# FPGA_CONFIG.net
KiCad netlist of a schematic drawn in Altium Designer
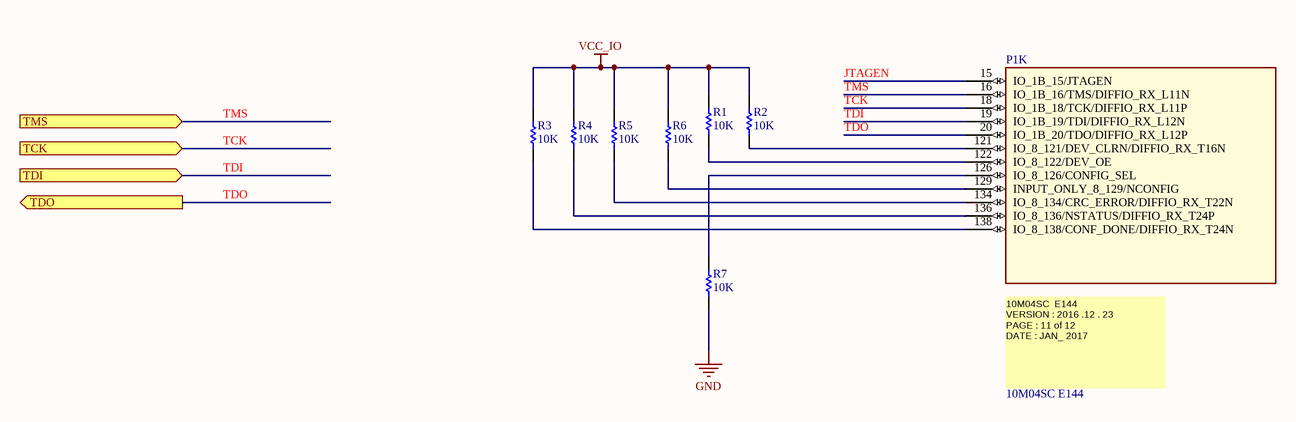
[diagram p0: FPGA_CONFIG.SchDoc]

(export (version "E")
  (design (tool "Eeschema 10.0.6"))
  (components
    (comp (ref "P1") (value "10M04SC E144") (libsource (lib "10m04sc_Library") (part "10M04SC E144")))
    (comp (ref "R1")
      (value "10K")
      (footprint "AXIAL-0.3")
      (description "Resistor")
      (fields (field (name "PUBLISHER") "Altium Limited"))
      (libsource (lib "Miscellaneous Devices") (part "Res1"))
    )
    (comp (ref "R2")
      (value "10K")
      (footprint "AXIAL-0.3")
      (description "Resistor")
      (fields (field (name "PUBLISHER") "Altium Limited"))
      (libsource (lib "Miscellaneous Devices") (part "Res1"))
    )
    (comp (ref "R3")
      (value "10K")
      (footprint "AXIAL-0.3")
      (description "Resistor")
      (fields (field (name "PUBLISHER") "Altium Limited"))
      (libsource (lib "Miscellaneous Devices") (part "Res1"))
    )
    (comp (ref "R4")
      (value "10K")
      (footprint "AXIAL-0.3")
      (description "Resistor")
      (fields (field (name "PUBLISHER") "Altium Limited"))
      (libsource (lib "Miscellaneous Devices") (part "Res1"))
    )
    (comp (ref "R5")
      (value "10K")
      (footprint "AXIAL-0.3")
      (description "Resistor")
      (fields (field (name "PUBLISHER") "Altium Limited"))
      (libsource (lib "Miscellaneous Devices") (part "Res1"))
    )
    (comp (ref "R6")
      (value "10K")
      (footprint "AXIAL-0.3")
      (description "Resistor")
      (fields (field (name "PUBLISHER") "Altium Limited"))
      (libsource (lib "Miscellaneous Devices") (part "Res1"))
    )
    (comp (ref "R7")
      (value "10K")
      (footprint "AXIAL-0.3")
      (description "Resistor")
      (fields (field (name "PUBLISHER") "Altium Limited"))
      (libsource (lib "Miscellaneous Devices") (part "Res1"))
    )
  )
  (nets
    (net (code "1") (name "/JTAGEN") (class "Default")
      (node (ref "P1") (pin "15") (pinfunction "IO_1B_15/JTAGEN_15") (pintype "bidirectional"))
    )
    (net (code "2") (name "/TCK") (class "Default")
      (node (ref "P1") (pin "18") (pinfunction "IO_1B_18/TCK/DIFFIO_RX_L11P_18") (pintype "bidirectional"))
    )
    (net (code "3") (name "/TDI") (class "Default")
      (node (ref "P1") (pin "19") (pinfunction "IO_1B_19/TDI/DIFFIO_RX_L12N_19") (pintype "bidirectional"))
    )
    (net (code "4") (name "/TDO") (class "Default")
      (node (ref "P1") (pin "20") (pinfunction "IO_1B_20/TDO/DIFFIO_RX_L12P_20") (pintype "bidirectional"))
    )
    (net (code "5") (name "/TMS") (class "Default")
      (node (ref "P1") (pin "16") (pinfunction "IO_1B_16/TMS/DIFFIO_RX_L11N_16") (pintype "bidirectional"))
    )
    (net (code "6") (name "GND") (class "Default")
      (node (ref "R7") (pin "1") (pinfunction "1_1") (pintype "passive"))
    )
    (net (code "7") (name "Net-(P1K-INPUT_ONLY_8_129{slash}NCONFIG)") (class "Default")
      (node (ref "P1") (pin "129") (pinfunction "INPUT_ONLY_8_129/NCONFIG_129") (pintype "bidirectional"))
      (node (ref "R6") (pin "1") (pinfunction "1_1") (pintype "passive"))
    )
    (net (code "8") (name "Net-(P1K-IO_8_121{slash}DEV_CLRN{slash}DIFFIO_RX_T16N)") (class "Default")
      (node (ref "P1") (pin "121") (pinfunction "IO_8_121/DEV_CLRN/DIFFIO_RX_T16N_121") (pintype "bidirectional"))
      (node (ref "R2") (pin "1") (pinfunction "1_1") (pintype "passive"))
    )
    (net (code "9") (name "Net-(P1K-IO_8_122{slash}DEV_OE)") (class "Default")
      (node (ref "P1") (pin "122") (pinfunction "IO_8_122/DEV_OE_122") (pintype "bidirectional"))
      (node (ref "R1") (pin "1") (pinfunction "1_1") (pintype "passive"))
    )
    (net (code "10") (name "Net-(P1K-IO_8_126{slash}CONFIG_SEL)") (class "Default")
      (node (ref "P1") (pin "126") (pinfunction "IO_8_126/CONFIG_SEL_126") (pintype "bidirectional"))
      (node (ref "R7") (pin "2") (pinfunction "2_2") (pintype "passive"))
    )
    (net (code "11") (name "Net-(P1K-IO_8_134{slash}CRC_ERROR{slash}DIFFIO_RX_T22N)") (class "Default")
      (node (ref "P1") (pin "134") (pinfunction "IO_8_134/CRC_ERROR/DIFFIO_RX_T22N_134") (pintype "bidirectional"))
      (node (ref "R5") (pin "1") (pinfunction "1_1") (pintype "passive"))
    )
    (net (code "12") (name "Net-(P1K-IO_8_136{slash}NSTATUS{slash}DIFFIO_RX_T24P)") (class "Default")
      (node (ref "P1") (pin "136") (pinfunction "IO_8_136/NSTATUS/DIFFIO_RX_T24P_136") (pintype "bidirectional"))
      (node (ref "R4") (pin "1") (pinfunction "1_1") (pintype "passive"))
    )
    (net (code "13") (name "Net-(P1K-IO_8_138{slash}CONF_DONE{slash}DIFFIO_RX_T24N)") (class "Default")
      (node (ref "P1") (pin "138") (pinfunction "IO_8_138/CONF_DONE/DIFFIO_RX_T24N_138") (pintype "bidirectional"))
      (node (ref "R3") (pin "1") (pinfunction "1_1") (pintype "passive"))
    )
    (net (code "14") (name "VCC_IO") (class "Default")
      (node (ref "R1") (pin "2") (pinfunction "2_2") (pintype "passive"))
      (node (ref "R2") (pin "2") (pinfunction "2_2") (pintype "passive"))
      (node (ref "R3") (pin "2") (pinfunction "2_2") (pintype "passive"))
      (node (ref "R4") (pin "2") (pinfunction "2_2") (pintype "passive"))
      (node (ref "R5") (pin "2") (pinfunction "2_2") (pintype "passive"))
      (node (ref "R6") (pin "2") (pinfunction "2_2") (pintype "passive"))
    )
  )
)
